# AttenuvertingVCA_Test.net
KiCad netlist of a schematic drawn in EAGLE
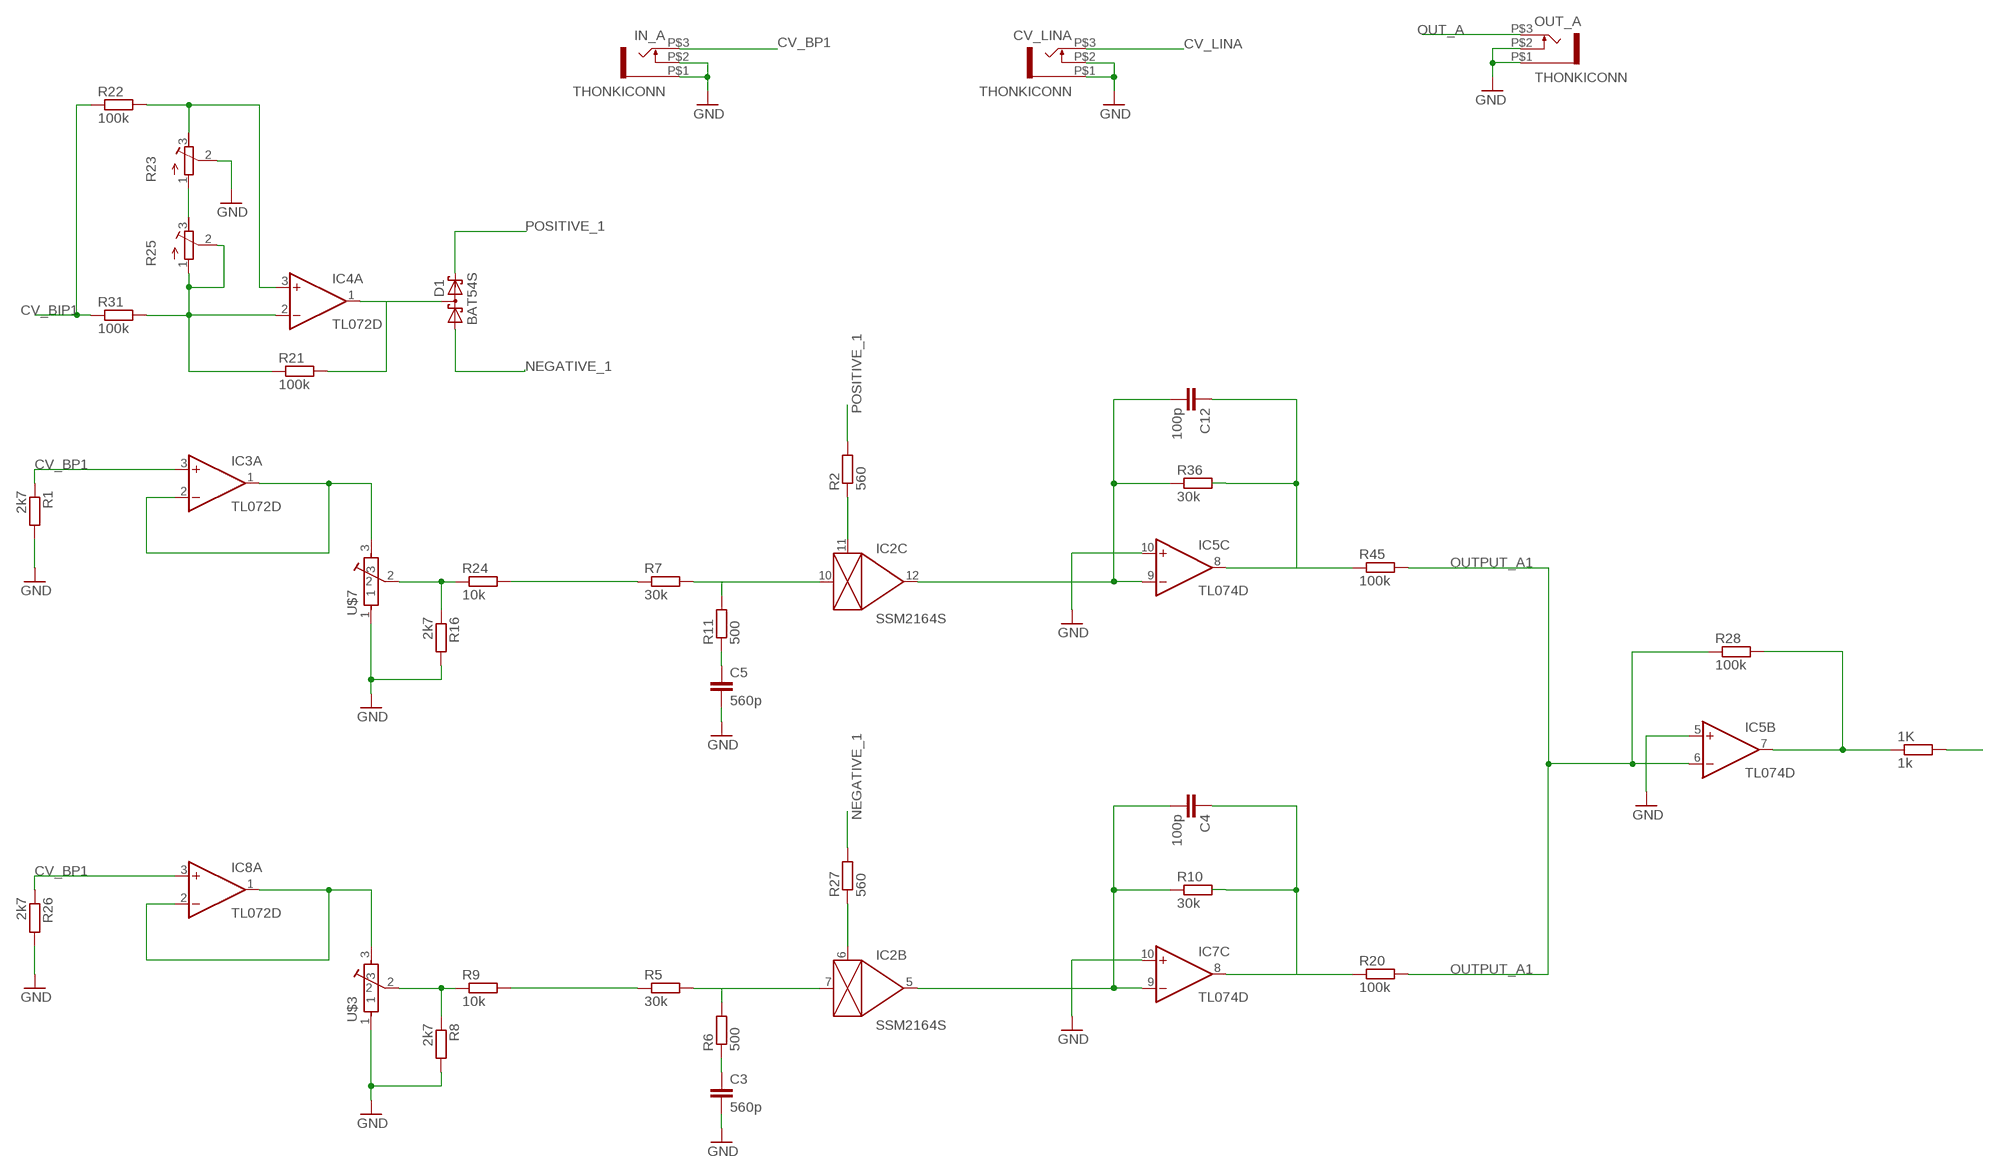
[diagram p0: schematic, sheet 1]

(export (version "E")
  (design (tool "Eeschema 10.0.6"))
  (components
    (comp (ref "1K")
      (value "1k")
      (footprint "eagle-import:0603")
      (libsource (lib "eagle-import") (part "R-EU_0603"))
    )
    (comp (ref "C3")
      (value "560p")
      (footprint "eagle-import:C0603K")
      (libsource (lib "eagle-import") (part "C-EUC0603K"))
    )
    (comp (ref "C4")
      (value "100p")
      (footprint "eagle-import:C0603K")
      (libsource (lib "eagle-import") (part "C-EUC0603K"))
    )
    (comp (ref "C5")
      (value "560p")
      (footprint "eagle-import:C0603K")
      (libsource (lib "eagle-import") (part "C-EUC0603K"))
    )
    (comp (ref "C12")
      (value "100p")
      (footprint "eagle-import:C0603K")
      (libsource (lib "eagle-import") (part "C-EUC0603K"))
    )
    (comp (ref "CV_LINA")
      (value "THONKICONN")
      (footprint "eagle-import:THONKICONN")
      (libsource (lib "eagle-import") (part "THONKICONN"))
    )
    (comp (ref "D1")
      (value "BAT54S")
      (footprint "eagle-import:SOT23")
      (libsource (lib "eagle-import") (part "BAT54S"))
    )
    (comp (ref "IC2")
      (value "SSM2164S")
      (footprint "eagle-import:SOIC16N")
      (libsource (lib "eagle-import") (part "SSM2164S"))
    )
    (comp (ref "IC3")
      (value "TL072D")
      (footprint "eagle-import:SO08")
      (libsource (lib "eagle-import") (part "TL072D"))
    )
    (comp (ref "IC4")
      (value "TL072D")
      (footprint "eagle-import:SO08")
      (libsource (lib "eagle-import") (part "TL072D"))
    )
    (comp (ref "IC5")
      (value "TL074D")
      (footprint "eagle-import:SO14")
      (libsource (lib "eagle-import") (part "TL074D"))
    )
    (comp (ref "IC7")
      (value "TL074D")
      (footprint "eagle-import:SO14")
      (libsource (lib "eagle-import") (part "TL074D"))
    )
    (comp (ref "IC8")
      (value "TL072D")
      (footprint "eagle-import:SO08")
      (libsource (lib "eagle-import") (part "TL072D"))
    )
    (comp (ref "IN_A")
      (value "THONKICONN")
      (footprint "eagle-import:THONKICONN")
      (libsource (lib "eagle-import") (part "THONKICONN"))
    )
    (comp (ref "OUT_A")
      (value "THONKICONN")
      (footprint "eagle-import:THONKICONN")
      (libsource (lib "eagle-import") (part "THONKICONN"))
    )
    (comp (ref "R1")
      (value "2k7")
      (footprint "eagle-import:0603")
      (libsource (lib "eagle-import") (part "R-EU_0603"))
    )
    (comp (ref "R2")
      (value "560")
      (footprint "eagle-import:0603")
      (libsource (lib "eagle-import") (part "R-EU_0603"))
    )
    (comp (ref "R5")
      (value "30k")
      (footprint "eagle-import:0603")
      (libsource (lib "eagle-import") (part "R-EU_0603"))
    )
    (comp (ref "R6")
      (value "500")
      (footprint "eagle-import:0603")
      (libsource (lib "eagle-import") (part "R-EU_0603"))
    )
    (comp (ref "R7")
      (value "30k")
      (footprint "eagle-import:0603")
      (libsource (lib "eagle-import") (part "R-EU_0603"))
    )
    (comp (ref "R8")
      (value "2k7")
      (footprint "eagle-import:0603")
      (libsource (lib "eagle-import") (part "R-EU_0603"))
    )
    (comp (ref "R9")
      (value "10k")
      (footprint "eagle-import:0603")
      (libsource (lib "eagle-import") (part "R-EU_0603"))
    )
    (comp (ref "R10")
      (value "30k")
      (footprint "eagle-import:0603")
      (libsource (lib "eagle-import") (part "R-EU_0603"))
    )
    (comp (ref "R11")
      (value "500")
      (footprint "eagle-import:0603")
      (libsource (lib "eagle-import") (part "R-EU_0603"))
    )
    (comp (ref "R16")
      (value "2k7")
      (footprint "eagle-import:0603")
      (libsource (lib "eagle-import") (part "R-EU_0603"))
    )
    (comp (ref "R20")
      (value "100k")
      (footprint "eagle-import:0603")
      (libsource (lib "eagle-import") (part "R-EU_0603"))
    )
    (comp (ref "R21")
      (value "100k")
      (footprint "eagle-import:0603")
      (libsource (lib "eagle-import") (part "R-EU_0603"))
    )
    (comp (ref "R22")
      (value "100k")
      (footprint "eagle-import:0603")
      (libsource (lib "eagle-import") (part "R-EU_0603"))
    )
    (comp (ref "R23")
      (value "R-TRIMM64X")
      (footprint "eagle-import:RTRIM64X")
      (libsource (lib "eagle-import") (part "R-TRIMM64X"))
    )
    (comp (ref "R24")
      (value "10k")
      (footprint "eagle-import:0603")
      (libsource (lib "eagle-import") (part "R-EU_0603"))
    )
    (comp (ref "R25")
      (value "R-TRIMM64X")
      (footprint "eagle-import:RTRIM64X")
      (libsource (lib "eagle-import") (part "R-TRIMM64X"))
    )
    (comp (ref "R26")
      (value "2k7")
      (footprint "eagle-import:0603")
      (libsource (lib "eagle-import") (part "R-EU_0603"))
    )
    (comp (ref "R27")
      (value "560")
      (footprint "eagle-import:0603")
      (libsource (lib "eagle-import") (part "R-EU_0603"))
    )
    (comp (ref "R28")
      (value "100k")
      (footprint "eagle-import:0603")
      (libsource (lib "eagle-import") (part "R-EU_0603"))
    )
    (comp (ref "R31")
      (value "100k")
      (footprint "eagle-import:0603")
      (libsource (lib "eagle-import") (part "R-EU_0603"))
    )
    (comp (ref "R36")
      (value "30k")
      (footprint "eagle-import:0603")
      (libsource (lib "eagle-import") (part "R-EU_0603"))
    )
    (comp (ref "R45")
      (value "100k")
      (footprint "eagle-import:0603")
      (libsource (lib "eagle-import") (part "R-EU_0603"))
    )
    (comp (ref "U$3")
      (value "POT-ALPS-RK09L1140")
      (footprint "eagle-import:POT-ALPS-RK09L1140")
      (libsource (lib "eagle-import") (part "POT-ALPS-RK09L1140"))
    )
    (comp (ref "U$7")
      (value "POT-ALPS-RK09L1140")
      (footprint "eagle-import:POT-ALPS-RK09L1140")
      (libsource (lib "eagle-import") (part "POT-ALPS-RK09L1140"))
    )
  )
  (nets
    (net (code "1") (name "/CV_BIP1") (class "Default")
      (node (ref "R22") (pin "1") (pinfunction "1_1") (pintype "passive"))
      (node (ref "R31") (pin "1") (pinfunction "1_1") (pintype "passive"))
    )
    (net (code "2") (name "/CV_BP1") (class "Default")
      (node (ref "IC3") (pin "3") (pinfunction "+IN_3") (pintype "input"))
      (node (ref "IC8") (pin "3") (pinfunction "+IN_3") (pintype "input"))
      (node (ref "IN_A") (pin "P$3") (pinfunction "3_P$3") (pintype "passive"))
      (node (ref "R1") (pin "1") (pinfunction "1_1") (pintype "passive"))
      (node (ref "R26") (pin "1") (pinfunction "1_1") (pintype "passive"))
    )
    (net (code "3") (name "/CV_LINA") (class "Default")
      (node (ref "CV_LINA") (pin "P$3") (pinfunction "3_P$3") (pintype "passive"))
    )
    (net (code "4") (name "/NEGATIVE_1") (class "Default")
      (node (ref "D1") (pin "1") (pinfunction "A1_1") (pintype "passive"))
      (node (ref "R27") (pin "2") (pinfunction "2_2") (pintype "passive"))
    )
    (net (code "5") (name "/OUTPUT_A1") (class "Default")
      (node (ref "IC5") (pin "6") (pinfunction "-IN_6") (pintype "input"))
      (node (ref "R20") (pin "2") (pinfunction "2_2") (pintype "passive"))
      (node (ref "R28") (pin "1") (pinfunction "1_1") (pintype "passive"))
      (node (ref "R45") (pin "2") (pinfunction "2_2") (pintype "passive"))
    )
    (net (code "6") (name "/OUT_A") (class "Default")
      (node (ref "OUT_A") (pin "P$3") (pinfunction "3_P$3") (pintype "passive"))
    )
    (net (code "7") (name "/POSITIVE_1") (class "Default")
      (node (ref "D1") (pin "2") (pinfunction "C2_2") (pintype "passive"))
      (node (ref "R2") (pin "2") (pinfunction "2_2") (pintype "passive"))
    )
    (net (code "8") (name "GND") (class "Default")
      (node (ref "C3") (pin "2") (pinfunction "2_2") (pintype "passive"))
      (node (ref "C5") (pin "2") (pinfunction "2_2") (pintype "passive"))
      (node (ref "CV_LINA") (pin "P$1") (pinfunction "5_P$1") (pintype "passive"))
      (node (ref "CV_LINA") (pin "P$2") (pinfunction "4_P$2") (pintype "passive"))
      (node (ref "IC5") (pin "10") (pinfunction "+IN_10") (pintype "input"))
      (node (ref "IC5") (pin "5") (pinfunction "+IN_5") (pintype "input"))
      (node (ref "IC7") (pin "10") (pinfunction "+IN_10") (pintype "input"))
      (node (ref "IN_A") (pin "P$1") (pinfunction "5_P$1") (pintype "passive"))
      (node (ref "IN_A") (pin "P$2") (pinfunction "4_P$2") (pintype "passive"))
      (node (ref "OUT_A") (pin "P$1") (pinfunction "5_P$1") (pintype "passive"))
      (node (ref "OUT_A") (pin "P$2") (pinfunction "4_P$2") (pintype "passive"))
      (node (ref "R1") (pin "2") (pinfunction "2_2") (pintype "passive"))
      (node (ref "R16") (pin "2") (pinfunction "2_2") (pintype "passive"))
      (node (ref "R23") (pin "2") (pinfunction "S_2") (pintype "passive"))
      (node (ref "R26") (pin "2") (pinfunction "2_2") (pintype "passive"))
      (node (ref "R8") (pin "2") (pinfunction "2_2") (pintype "passive"))
      (node (ref "U$3") (pin "1") (pinfunction "1_1") (pintype "bidirectional"))
      (node (ref "U$7") (pin "1") (pinfunction "1_1") (pintype "bidirectional"))
    )
    (net (code "9") (name "Net-(C3-Pad1)") (class "Default")
      (node (ref "C3") (pin "1") (pinfunction "1_1") (pintype "passive"))
      (node (ref "R6") (pin "1") (pinfunction "1_1") (pintype "passive"))
    )
    (net (code "10") (name "Net-(C5-Pad1)") (class "Default")
      (node (ref "C5") (pin "1") (pinfunction "1_1") (pintype "passive"))
      (node (ref "R11") (pin "1") (pinfunction "1_1") (pintype "passive"))
    )
    (net (code "11") (name "Net-(D1-C1A2)") (class "Default")
      (node (ref "D1") (pin "3") (pinfunction "C1A2_3") (pintype "passive"))
      (node (ref "IC4") (pin "1") (pinfunction "OUT_1") (pintype "output"))
      (node (ref "R21") (pin "2") (pinfunction "2_2") (pintype "passive"))
    )
    (net (code "12") (name "Net-(IC2B-CTRL)") (class "Default")
      (node (ref "IC2") (pin "6") (pinfunction "CTRL_6") (pintype "input"))
      (node (ref "R27") (pin "1") (pinfunction "1_1") (pintype "passive"))
    )
    (net (code "13") (name "Net-(IC2B-IN)") (class "Default")
      (node (ref "IC2") (pin "7") (pinfunction "IN_7") (pintype "input"))
      (node (ref "R5") (pin "2") (pinfunction "2_2") (pintype "passive"))
      (node (ref "R6") (pin "2") (pinfunction "2_2") (pintype "passive"))
    )
    (net (code "14") (name "Net-(IC2B-OUT)") (class "Default")
      (node (ref "C4") (pin "2") (pinfunction "2_2") (pintype "passive"))
      (node (ref "IC2") (pin "5") (pinfunction "OUT_5") (pintype "output"))
      (node (ref "IC7") (pin "9") (pinfunction "-IN_9") (pintype "input"))
      (node (ref "R10") (pin "1") (pinfunction "1_1") (pintype "passive"))
    )
    (net (code "15") (name "Net-(IC2C-CTRL)") (class "Default")
      (node (ref "IC2") (pin "11") (pinfunction "CTRL_11") (pintype "input"))
      (node (ref "R2") (pin "1") (pinfunction "1_1") (pintype "passive"))
    )
    (net (code "16") (name "Net-(IC2C-IN)") (class "Default")
      (node (ref "IC2") (pin "10") (pinfunction "IN_10") (pintype "input"))
      (node (ref "R11") (pin "2") (pinfunction "2_2") (pintype "passive"))
      (node (ref "R7") (pin "2") (pinfunction "2_2") (pintype "passive"))
    )
    (net (code "17") (name "Net-(IC2C-OUT)") (class "Default")
      (node (ref "C12") (pin "2") (pinfunction "2_2") (pintype "passive"))
      (node (ref "IC2") (pin "12") (pinfunction "OUT_12") (pintype "output"))
      (node (ref "IC5") (pin "9") (pinfunction "-IN_9") (pintype "input"))
      (node (ref "R36") (pin "1") (pinfunction "1_1") (pintype "passive"))
    )
    (net (code "18") (name "Net-(IC3A--IN)") (class "Default")
      (node (ref "IC3") (pin "1") (pinfunction "OUT_1") (pintype "output"))
      (node (ref "IC3") (pin "2") (pinfunction "-IN_2") (pintype "input"))
      (node (ref "U$7") (pin "3") (pinfunction "3_3") (pintype "bidirectional"))
    )
    (net (code "19") (name "Net-(IC4A-+IN)") (class "Default")
      (node (ref "IC4") (pin "3") (pinfunction "+IN_3") (pintype "input"))
      (node (ref "R22") (pin "2") (pinfunction "2_2") (pintype "passive"))
      (node (ref "R23") (pin "3") (pinfunction "E_3") (pintype "passive"))
    )
    (net (code "20") (name "Net-(IC4A--IN)") (class "Default")
      (node (ref "IC4") (pin "2") (pinfunction "-IN_2") (pintype "input"))
      (node (ref "R21") (pin "1") (pinfunction "1_1") (pintype "passive"))
      (node (ref "R25") (pin "1") (pinfunction "A_1") (pintype "passive"))
      (node (ref "R25") (pin "2") (pinfunction "S_2") (pintype "passive"))
      (node (ref "R31") (pin "2") (pinfunction "2_2") (pintype "passive"))
    )
    (net (code "21") (name "Net-(IC5B-OUT)") (class "Default")
      (node (ref "1K") (pin "1") (pinfunction "1_1") (pintype "passive"))
      (node (ref "IC5") (pin "7") (pinfunction "OUT_7") (pintype "output"))
      (node (ref "R28") (pin "2") (pinfunction "2_2") (pintype "passive"))
    )
    (net (code "22") (name "Net-(IC5C-OUT)") (class "Default")
      (node (ref "C12") (pin "1") (pinfunction "1_1") (pintype "passive"))
      (node (ref "IC5") (pin "8") (pinfunction "OUT_8") (pintype "output"))
      (node (ref "R36") (pin "2") (pinfunction "2_2") (pintype "passive"))
      (node (ref "R45") (pin "1") (pinfunction "1_1") (pintype "passive"))
    )
    (net (code "23") (name "Net-(IC7C-OUT)") (class "Default")
      (node (ref "C4") (pin "1") (pinfunction "1_1") (pintype "passive"))
      (node (ref "IC7") (pin "8") (pinfunction "OUT_8") (pintype "output"))
      (node (ref "R10") (pin "2") (pinfunction "2_2") (pintype "passive"))
      (node (ref "R20") (pin "1") (pinfunction "1_1") (pintype "passive"))
    )
    (net (code "24") (name "Net-(IC8A--IN)") (class "Default")
      (node (ref "IC8") (pin "1") (pinfunction "OUT_1") (pintype "output"))
      (node (ref "IC8") (pin "2") (pinfunction "-IN_2") (pintype "input"))
      (node (ref "U$3") (pin "3") (pinfunction "3_3") (pintype "bidirectional"))
    )
    (net (code "25") (name "Net-(R5-Pad1)") (class "Default")
      (node (ref "R5") (pin "1") (pinfunction "1_1") (pintype "passive"))
      (node (ref "R9") (pin "2") (pinfunction "2_2") (pintype "passive"))
    )
    (net (code "26") (name "Net-(R8-Pad1)") (class "Default")
      (node (ref "R8") (pin "1") (pinfunction "1_1") (pintype "passive"))
      (node (ref "R9") (pin "1") (pinfunction "1_1") (pintype "passive"))
      (node (ref "U$3") (pin "2") (pinfunction "2_2") (pintype "bidirectional"))
    )
    (net (code "27") (name "Net-(R16-Pad1)") (class "Default")
      (node (ref "R16") (pin "1") (pinfunction "1_1") (pintype "passive"))
      (node (ref "R24") (pin "1") (pinfunction "1_1") (pintype "passive"))
      (node (ref "U$7") (pin "2") (pinfunction "2_2") (pintype "bidirectional"))
    )
    (net (code "28") (name "Net-(R23-A)") (class "Default")
      (node (ref "R23") (pin "1") (pinfunction "A_1") (pintype "passive"))
      (node (ref "R25") (pin "3") (pinfunction "E_3") (pintype "passive"))
    )
    (net (code "29") (name "Net-(R24-Pad2)") (class "Default")
      (node (ref "R24") (pin "2") (pinfunction "2_2") (pintype "passive"))
      (node (ref "R7") (pin "1") (pinfunction "1_1") (pintype "passive"))
    )
    (net (code "30") (name "unconnected-(1K-Pad2)") (class "Default")
      (node (ref "1K") (pin "2") (pinfunction "2_2") (pintype "passive"))
    )
  )
)
